# Enclosure_Front.net
KiCad netlist of a schematic drawn in EAGLE
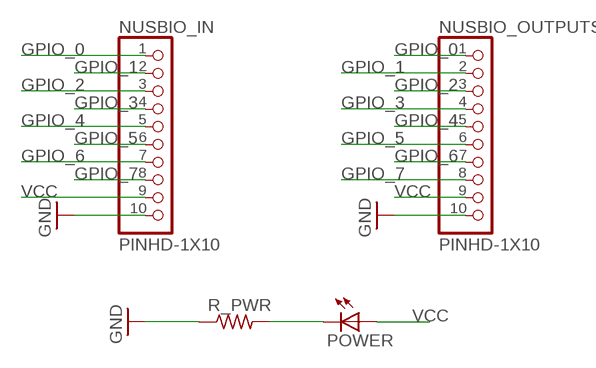
[diagram p0: schematic, sheet 1]

(export (version "E")
  (design (tool "Eeschema 10.0.6"))
  (components
    (comp (ref "NUSBIO_IN")
      (value "PINHD-1X10")
      (footprint "eagle-import:1X10-BIG")
      (libsource (lib "eagle-import") (part "PINHD-1X10"))
    )
    (comp (ref "NUSBIO_OUTPUTS")
      (value "PINHD-1X10")
      (footprint "eagle-import:1X10-BIG")
      (libsource (lib "eagle-import") (part "PINHD-1X10"))
    )
    (comp (ref "POWER")
      (value "LEDSMT1206")
      (footprint "eagle-import:1206")
      (libsource (lib "eagle-import") (part "LEDSMT1206"))
    )
    (comp (ref "R_PWR")
      (value "R-US_R1206")
      (footprint "eagle-import:R1206")
      (libsource (lib "eagle-import") (part "R-US_R1206"))
    )
  )
  (nets
    (net (code "1") (name "/GPIO_0") (class "Default")
      (node (ref "NUSBIO_IN") (pin "1") (pinfunction "1_1") (pintype "passive"))
      (node (ref "NUSBIO_OUTPUTS") (pin "1") (pinfunction "1_1") (pintype "passive"))
    )
    (net (code "2") (name "/GPIO_1") (class "Default")
      (node (ref "NUSBIO_IN") (pin "2") (pinfunction "2_2") (pintype "passive"))
      (node (ref "NUSBIO_OUTPUTS") (pin "2") (pinfunction "2_2") (pintype "passive"))
    )
    (net (code "3") (name "/GPIO_2") (class "Default")
      (node (ref "NUSBIO_IN") (pin "3") (pinfunction "3_3") (pintype "passive"))
      (node (ref "NUSBIO_OUTPUTS") (pin "3") (pinfunction "3_3") (pintype "passive"))
    )
    (net (code "4") (name "/GPIO_3") (class "Default")
      (node (ref "NUSBIO_IN") (pin "4") (pinfunction "4_4") (pintype "passive"))
      (node (ref "NUSBIO_OUTPUTS") (pin "4") (pinfunction "4_4") (pintype "passive"))
    )
    (net (code "5") (name "/GPIO_4") (class "Default")
      (node (ref "NUSBIO_IN") (pin "5") (pinfunction "5_5") (pintype "passive"))
      (node (ref "NUSBIO_OUTPUTS") (pin "5") (pinfunction "5_5") (pintype "passive"))
    )
    (net (code "6") (name "/GPIO_5") (class "Default")
      (node (ref "NUSBIO_IN") (pin "6") (pinfunction "6_6") (pintype "passive"))
      (node (ref "NUSBIO_OUTPUTS") (pin "6") (pinfunction "6_6") (pintype "passive"))
    )
    (net (code "7") (name "/GPIO_6") (class "Default")
      (node (ref "NUSBIO_IN") (pin "7") (pinfunction "7_7") (pintype "passive"))
      (node (ref "NUSBIO_OUTPUTS") (pin "7") (pinfunction "7_7") (pintype "passive"))
    )
    (net (code "8") (name "/GPIO_7") (class "Default")
      (node (ref "NUSBIO_IN") (pin "8") (pinfunction "8_8") (pintype "passive"))
      (node (ref "NUSBIO_OUTPUTS") (pin "8") (pinfunction "8_8") (pintype "passive"))
    )
    (net (code "9") (name "/VCC") (class "Default")
      (node (ref "NUSBIO_IN") (pin "9") (pinfunction "9_9") (pintype "passive"))
      (node (ref "NUSBIO_OUTPUTS") (pin "9") (pinfunction "9_9") (pintype "passive"))
      (node (ref "POWER") (pin "A") (pinfunction "A_A") (pintype "passive"))
    )
    (net (code "10") (name "GND") (class "Default")
      (node (ref "NUSBIO_IN") (pin "10") (pinfunction "10_10") (pintype "passive"))
      (node (ref "NUSBIO_OUTPUTS") (pin "10") (pinfunction "10_10") (pintype "passive"))
      (node (ref "R_PWR") (pin "1") (pinfunction "1_1") (pintype "passive"))
    )
    (net (code "11") (name "Net-(POWER-PadC)") (class "Default")
      (node (ref "POWER") (pin "C") (pinfunction "C_C") (pintype "passive"))
      (node (ref "R_PWR") (pin "2") (pinfunction "2_2") (pintype "passive"))
    )
  )
)
